# mp28164-buck-boost-flashlight-driver-17m.net
KiCad netlist of a schematic drawn in EAGLE
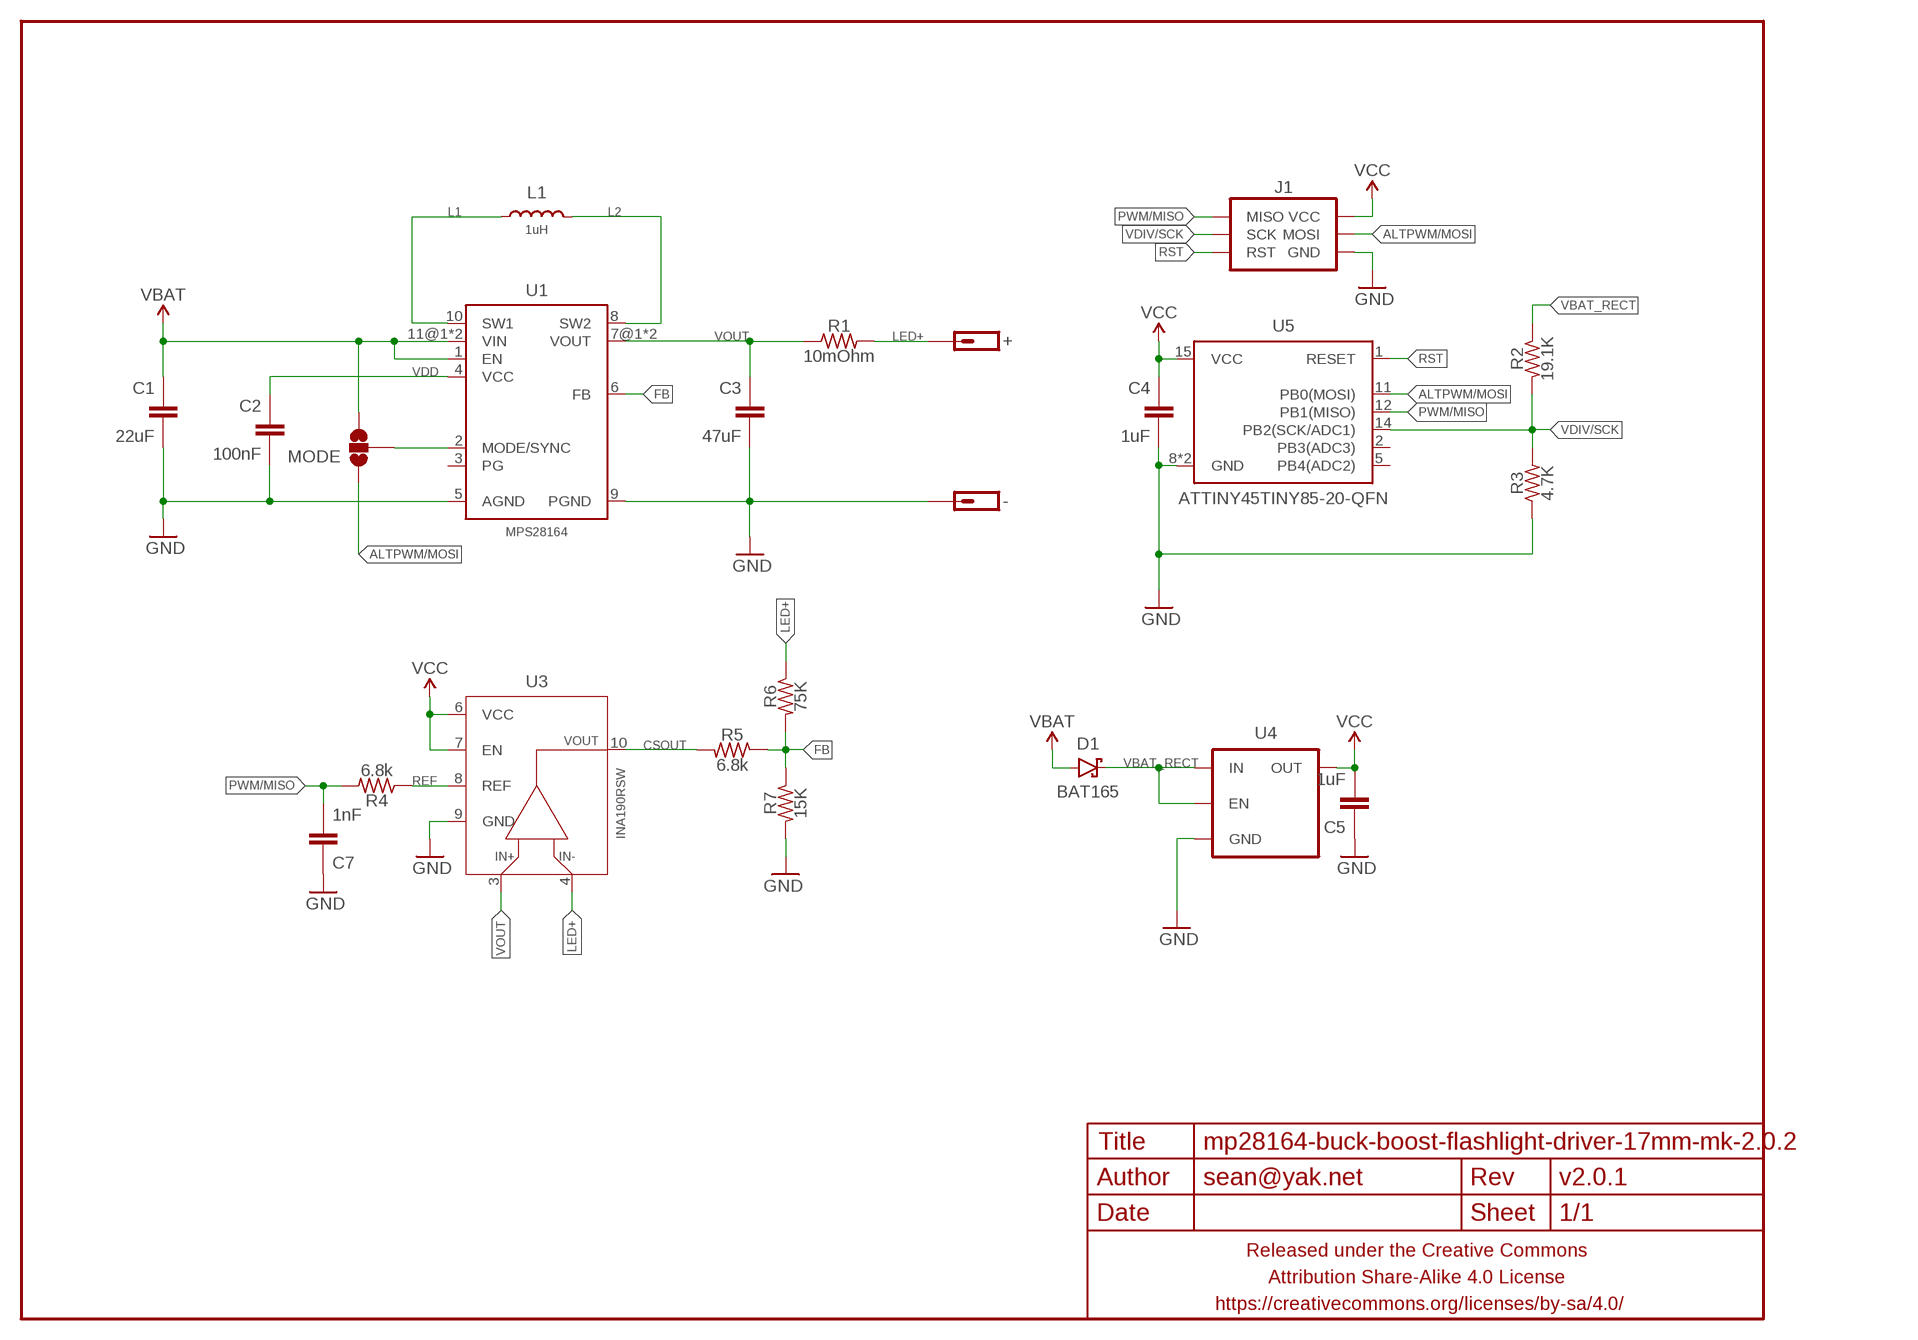
[diagram p0: schematic, sheet 1]

(export (version "E")
  (design (tool "Eeschema 10.0.6"))
  (components
    (comp (ref "+")
      (value "M01SMD-1.6MMX3.2MM-NS")
      (footprint "eagle-import:1X01-SMD-1.6MMX3.2MM-NS")
      (libsource (lib "eagle-import") (part "M01SMD-1.6MMX3.2MM-NS"))
    )
    (comp (ref "-")
      (value "M01SMD-1.6MMX3.2MM-NS")
      (footprint "eagle-import:1X01-SMD-1.6MMX3.2MM-NS")
      (libsource (lib "eagle-import") (part "M01SMD-1.6MMX3.2MM-NS"))
    )
    (comp (ref "C1")
      (value "22uF")
      (footprint "eagle-import:C1206")
      (libsource (lib "eagle-import") (part "CAPACITOR-CERAMICC1206"))
    )
    (comp (ref "C2")
      (value "100nF")
      (footprint "eagle-import:C0402")
      (libsource (lib "eagle-import") (part "CAPACITOR-CERAMICC0402"))
    )
    (comp (ref "C3")
      (value "47uF")
      (footprint "eagle-import:C1206")
      (libsource (lib "eagle-import") (part "CAPACITOR-CERAMICC1206"))
    )
    (comp (ref "C4")
      (value "1uF")
      (footprint "eagle-import:C0402")
      (libsource (lib "eagle-import") (part "CAPACITOR-CERAMICC0402"))
    )
    (comp (ref "C5")
      (value "1uF")
      (footprint "eagle-import:C0402")
      (libsource (lib "eagle-import") (part "CAPACITOR-CERAMICC0402"))
    )
    (comp (ref "C7")
      (value "1nF")
      (footprint "eagle-import:C0402")
      (libsource (lib "eagle-import") (part "CAPACITOR-CERAMICC0402"))
    )
    (comp (ref "D1")
      (value "BAT165")
      (footprint "eagle-import:SOD323-SCHOTTKY")
      (libsource (lib "eagle-import") (part "DIODE-SCHOTTKYSOD323"))
    )
    (comp (ref "FRAME1")
      (value "FRAME-LETTERNO_PACKAGE")
      (footprint "eagle-import:DUMMY")
      (fields
        (field (name "DESIGNER") "sean@yak.net")
        (field (name "VERSION") "v2.0.1")
        (field (name "DESIGNER_1") "sean@yak.net")
        (field (name "VERSION_1") "v2.0.1")
      )
      (libsource (lib "eagle-import") (part "FRAME-LETTERNO_PACKAGE"))
    )
    (comp (ref "J1")
      (value "AVR_SPI_PRG_6SMD-1.27MM")
      (footprint "eagle-import:2X3-1.27MM-SMD")
      (libsource (lib "eagle-import") (part "AVR_SPI_PRG_6SMD-1.27MM"))
    )
    (comp (ref "L1")
      (value "1uH")
      (footprint "eagle-import:XAL7070")
      (libsource (lib "eagle-import") (part "INDUCTORXAL7070"))
    )
    (comp (ref "MODE")
      (value "JUMPER-PAD-3-NOSMALLER_BOX_SILK")
      (footprint "eagle-import:PAD-JUMPER-3-NO_YES_SILK_SMALLER_BOX")
      (libsource (lib "eagle-import") (part "JUMPER-PAD-3-NOSMALLER_BOX_SILK"))
    )
    (comp (ref "R1")
      (value "10mOhm")
      (footprint "eagle-import:R1206")
      (libsource (lib "eagle-import") (part "RESISTORR1206"))
    )
    (comp (ref "R2")
      (value "19.1K")
      (footprint "eagle-import:R0402")
      (libsource (lib "eagle-import") (part "RESISTORR0402"))
    )
    (comp (ref "R3")
      (value "4.7K")
      (footprint "eagle-import:R0402")
      (libsource (lib "eagle-import") (part "RESISTORR0402"))
    )
    (comp (ref "R4")
      (value "6.8k")
      (footprint "eagle-import:R0402")
      (libsource (lib "eagle-import") (part "RESISTORR0402"))
    )
    (comp (ref "R5")
      (value "6.8k")
      (footprint "eagle-import:R0402")
      (libsource (lib "eagle-import") (part "RESISTORR0402"))
    )
    (comp (ref "R6")
      (value "75K")
      (footprint "eagle-import:R0402")
      (libsource (lib "eagle-import") (part "RESISTORR0402"))
    )
    (comp (ref "R7")
      (value "15K")
      (footprint "eagle-import:R0402")
      (libsource (lib "eagle-import") (part "RESISTORR0402"))
    )
    (comp (ref "U1")
      (value "MPS28164")
      (footprint "eagle-import:MPS28164")
      (libsource (lib "eagle-import") (part "MPS28164"))
    )
    (comp (ref "U3")
      (value "INA190RSW")
      (footprint "eagle-import:UQFN-10")
      (libsource (lib "eagle-import") (part "INA190RSW"))
    )
    (comp (ref "U4")
      (value "V_REG_ENTLV700")
      (footprint "eagle-import:SC70")
      (libsource (lib "eagle-import") (part "V_REG_ENTLV700"))
    )
    (comp (ref "U5")
      (value "ATTINY45TINY85-20-QFN")
      (footprint "eagle-import:QFN20")
      (libsource (lib "eagle-import") (part "ATTINY45TINY85-20-QFN"))
    )
  )
  (nets
    (net (code "1") (name "/CSOUT") (class "Default")
      (node (ref "R5") (pin "2") (pinfunction "2_2") (pintype "passive"))
      (node (ref "U3") (pin "10") (pinfunction "OUT_10") (pintype "bidirectional"))
    )
    (net (code "2") (name "/L1") (class "Default")
      (node (ref "L1") (pin "P$1") (pinfunction "1_P$1") (pintype "passive"))
      (node (ref "U1") (pin "10") (pinfunction "SW1_10") (pintype "bidirectional"))
    )
    (net (code "3") (name "/L2") (class "Default")
      (node (ref "L1") (pin "P$2") (pinfunction "2_P$2") (pintype "passive"))
      (node (ref "U1") (pin "8") (pinfunction "SW2_8") (pintype "bidirectional"))
    )
    (net (code "4") (name "/REF") (class "Default")
      (node (ref "R4") (pin "1") (pinfunction "1_1") (pintype "passive"))
      (node (ref "U3") (pin "8") (pinfunction "REF_8") (pintype "bidirectional"))
    )
    (net (code "5") (name "/VDD") (class "Default")
      (node (ref "C2") (pin "1") (pinfunction "1_1") (pintype "passive"))
      (node (ref "U1") (pin "4") (pinfunction "VCC_4") (pintype "bidirectional"))
    )
    (net (code "6") (name "ALTPWM{slash}MOSI") (class "Default")
      (node (ref "J1") (pin "4") (pinfunction "MOSI_4") (pintype "passive"))
      (node (ref "MODE") (pin "1") (pinfunction "1_1") (pintype "passive"))
      (node (ref "U5") (pin "11") (pinfunction "PB0(MOSI)_11") (pintype "bidirectional"))
    )
    (net (code "7") (name "FB") (class "Default")
      (node (ref "R5") (pin "1") (pinfunction "1_1") (pintype "passive"))
      (node (ref "R6") (pin "2") (pinfunction "2_2") (pintype "passive"))
      (node (ref "R7") (pin "1") (pinfunction "1_1") (pintype "passive"))
      (node (ref "U1") (pin "6") (pinfunction "FB_6") (pintype "bidirectional"))
    )
    (net (code "8") (name "GND") (class "Default")
      (node (ref "-") (pin "P$1") (pinfunction "1_P$1") (pintype "passive"))
      (node (ref "C1") (pin "2") (pinfunction "2_2") (pintype "passive"))
      (node (ref "C2") (pin "2") (pinfunction "2_2") (pintype "passive"))
      (node (ref "C3") (pin "2") (pinfunction "2_2") (pintype "passive"))
      (node (ref "C4") (pin "2") (pinfunction "2_2") (pintype "passive"))
      (node (ref "C5") (pin "1") (pinfunction "1_1") (pintype "passive"))
      (node (ref "C7") (pin "1") (pinfunction "1_1") (pintype "passive"))
      (node (ref "J1") (pin "6") (pinfunction "GND_6") (pintype "passive"))
      (node (ref "R3") (pin "1") (pinfunction "1_1") (pintype "passive"))
      (node (ref "R7") (pin "2") (pinfunction "2_2") (pintype "passive"))
      (node (ref "U1") (pin "5") (pinfunction "AGND_5") (pintype "bidirectional"))
      (node (ref "U1") (pin "9") (pinfunction "PGND_9") (pintype "bidirectional"))
      (node (ref "U3") (pin "9") (pinfunction "GND_9") (pintype "bidirectional"))
      (node (ref "U4") (pin "2") (pinfunction "GND_2") (pintype "input"))
      (node (ref "U5") (pin "8") (pinfunction "GND_8") (pintype "bidirectional"))
      (node (ref "U5") (pin "PAD") (pinfunction "GND_PAD") (pintype "bidirectional"))
    )
    (net (code "9") (name "LED+") (class "Default")
      (node (ref "+") (pin "P$1") (pinfunction "1_P$1") (pintype "passive"))
      (node (ref "R1") (pin "2") (pinfunction "2_2") (pintype "passive"))
      (node (ref "R6") (pin "1") (pinfunction "1_1") (pintype "passive"))
      (node (ref "U3") (pin "4") (pinfunction "VIN-_4") (pintype "bidirectional"))
    )
    (net (code "10") (name "Net-(U1-MODE{slash}SYNC)") (class "Default")
      (node (ref "MODE") (pin "2") (pinfunction "2_2") (pintype "passive"))
      (node (ref "U1") (pin "2") (pinfunction "MODE/SYNC_2") (pintype "bidirectional"))
    )
    (net (code "11") (name "PWM{slash}MISO") (class "Default")
      (node (ref "C7") (pin "2") (pinfunction "2_2") (pintype "passive"))
      (node (ref "J1") (pin "1") (pinfunction "MISO_1") (pintype "passive"))
      (node (ref "R4") (pin "2") (pinfunction "2_2") (pintype "passive"))
      (node (ref "U5") (pin "12") (pinfunction "PB1(MISO)_12") (pintype "bidirectional"))
    )
    (net (code "12") (name "RST") (class "Default")
      (node (ref "J1") (pin "5") (pinfunction "RST_5") (pintype "passive"))
      (node (ref "U5") (pin "1") (pinfunction "RESET_1") (pintype "bidirectional"))
    )
    (net (code "13") (name "VBAT") (class "Default")
      (node (ref "C1") (pin "1") (pinfunction "1_1") (pintype "passive"))
      (node (ref "D1") (pin "A") (pinfunction "A_A") (pintype "passive"))
      (node (ref "MODE") (pin "3") (pinfunction "3_3") (pintype "passive"))
      (node (ref "U1") (pin "1") (pinfunction "EN_1") (pintype "bidirectional"))
      (node (ref "U1") (pin "11@1") (pinfunction "VIN_11@1") (pintype "bidirectional"))
      (node (ref "U1") (pin "11@2") (pinfunction "VIN_11@2") (pintype "bidirectional"))
    )
    (net (code "14") (name "VBAT_RECT") (class "Default")
      (node (ref "D1") (pin "C") (pinfunction "C_C") (pintype "passive"))
      (node (ref "R2") (pin "1") (pinfunction "1_1") (pintype "passive"))
      (node (ref "U4") (pin "1") (pinfunction "IN_1") (pintype "input"))
      (node (ref "U4") (pin "3") (pinfunction "EN_3") (pintype "input"))
    )
    (net (code "15") (name "VCC") (class "Default")
      (node (ref "C4") (pin "1") (pinfunction "1_1") (pintype "passive"))
      (node (ref "C5") (pin "2") (pinfunction "2_2") (pintype "passive"))
      (node (ref "J1") (pin "2") (pinfunction "VCC_2") (pintype "passive"))
      (node (ref "U3") (pin "6") (pinfunction "VCC_6") (pintype "bidirectional"))
      (node (ref "U3") (pin "7") (pinfunction "EN_7") (pintype "bidirectional"))
      (node (ref "U4") (pin "5") (pinfunction "OUT_5") (pintype "passive"))
      (node (ref "U5") (pin "15") (pinfunction "VCC_15") (pintype "bidirectional"))
    )
    (net (code "16") (name "VDIV{slash}SCK") (class "Default")
      (node (ref "J1") (pin "3") (pinfunction "SCK_3") (pintype "passive"))
      (node (ref "R2") (pin "2") (pinfunction "2_2") (pintype "passive"))
      (node (ref "R3") (pin "2") (pinfunction "2_2") (pintype "passive"))
      (node (ref "U5") (pin "14") (pinfunction "PB2(SCK/ADC1)_14") (pintype "bidirectional"))
    )
    (net (code "17") (name "VOUT") (class "Default")
      (node (ref "C3") (pin "1") (pinfunction "1_1") (pintype "passive"))
      (node (ref "R1") (pin "1") (pinfunction "1_1") (pintype "passive"))
      (node (ref "U1") (pin "7@1") (pinfunction "VOUT_7@1") (pintype "bidirectional"))
      (node (ref "U1") (pin "7@2") (pinfunction "VOUT_7@2") (pintype "bidirectional"))
      (node (ref "U3") (pin "3") (pinfunction "VIN+_3") (pintype "bidirectional"))
    )
    (net (code "18") (name "unconnected-(U1-PG-Pad3)") (class "Default")
      (node (ref "U1") (pin "3") (pinfunction "PG_3") (pintype "bidirectional"))
    )
    (net (code "19") (name "unconnected-(U5-PB3(ADC3)-Pad2)") (class "Default")
      (node (ref "U5") (pin "2") (pinfunction "PB3(ADC3)_2") (pintype "bidirectional"))
    )
    (net (code "20") (name "unconnected-(U5-PB4(ADC2)-Pad5)") (class "Default")
      (node (ref "U5") (pin "5") (pinfunction "PB4(ADC2)_5") (pintype "bidirectional"))
    )
  )
)
